# Programmable_Delay_Line.net
KiCad netlist of a schematic drawn in Altium Designer
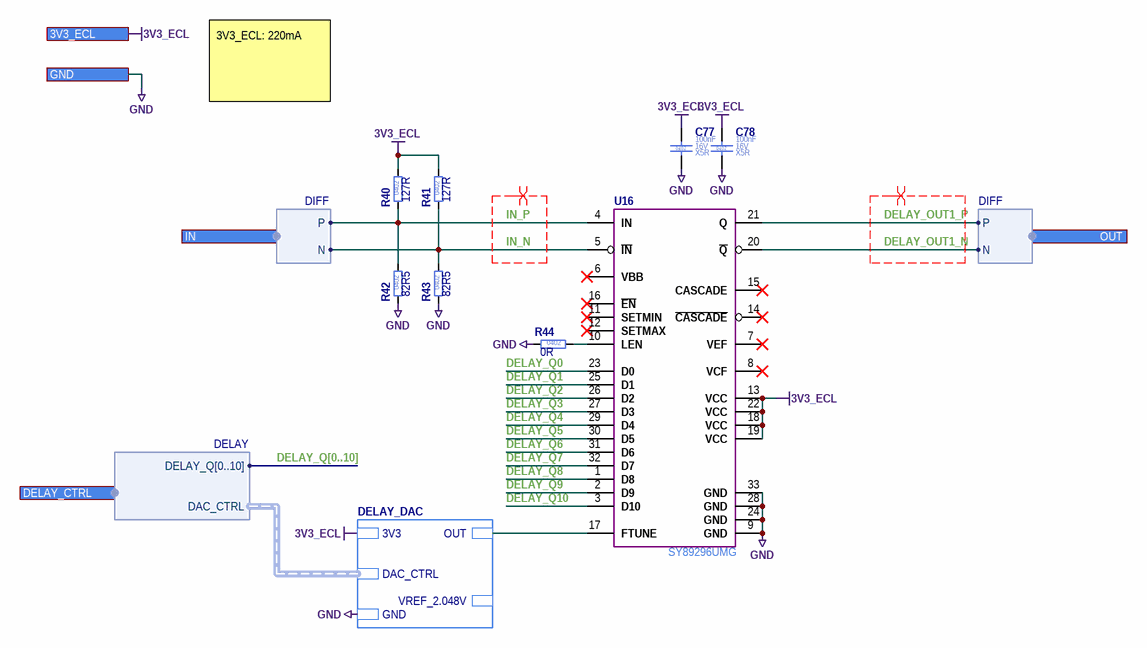
[diagram p0: Programmable_Delay_Line.SchDoc]

(export (version "E")
  (design (tool "Eeschema 10.0.6"))
  (components
    (comp (ref "C77")
      (value "C_100NF_16V_X5R_0402_10")
      (footprint "C_0402_1005")
      (description "Ceramic Capacitor")
      (fields
        (field (name "CASE/PACKAGE") "0402")
        (field (name "VOLTAGE RATING (DC)") "16V")
        (field (name "DIELECTRIC") "X5R")
        (field (name "CAPACITANCE") "100nF")
        (field (name "TOLERANCE") "10%")
        (field (name "MANUFACTURER PART NUMBER") "EMK105BJ104KV-F")
      )
      (libsource (lib "7Sigma") (part "C"))
    )
    (comp (ref "C78")
      (value "C_100NF_16V_X5R_0402_10")
      (footprint "C_0402_1005")
      (description "Ceramic Capacitor")
      (fields
        (field (name "CASE/PACKAGE") "0402")
        (field (name "VOLTAGE RATING (DC)") "16V")
        (field (name "DIELECTRIC") "X5R")
        (field (name "CAPACITANCE") "100nF")
        (field (name "TOLERANCE") "10%")
        (field (name "MANUFACTURER PART NUMBER") "EMK105BJ104KV-F")
      )
      (libsource (lib "7Sigma") (part "C"))
    )
    (comp (ref "R40")
      (value "R_127R_0402_1")
      (footprint "R_0402_1005")
      (description "Thick Film Resistor")
      (fields
        (field (name "RESISTANCE") "127R")
        (field (name "CASE/PACKAGE") "0402")
        (field (name "TOLERANCE") "1%")
        (field (name "MANUFACTURER") "Yageo")
      )
      (libsource (lib "7Sigma") (part "R"))
    )
    (comp (ref "R41")
      (value "R_127R_0402_1")
      (footprint "R_0402_1005")
      (description "Thick Film Resistor")
      (fields
        (field (name "RESISTANCE") "127R")
        (field (name "CASE/PACKAGE") "0402")
        (field (name "TOLERANCE") "1%")
        (field (name "MANUFACTURER") "Yageo")
      )
      (libsource (lib "7Sigma") (part "R"))
    )
    (comp (ref "R42")
      (value "R_82R5_0402_1")
      (footprint "R_0402_1005")
      (description "Thick Film Resistor")
      (fields
        (field (name "RESISTANCE") "82R5")
        (field (name "CASE/PACKAGE") "0402")
        (field (name "TOLERANCE") "1%")
        (field (name "MANUFACTURER") "Yageo")
      )
      (libsource (lib "7Sigma") (part "R"))
    )
    (comp (ref "R43")
      (value "R_82R5_0402_1")
      (footprint "R_0402_1005")
      (description "Thick Film Resistor")
      (fields
        (field (name "RESISTANCE") "82R5")
        (field (name "CASE/PACKAGE") "0402")
        (field (name "TOLERANCE") "1%")
        (field (name "MANUFACTURER") "Yageo")
      )
      (libsource (lib "7Sigma") (part "R"))
    )
    (comp (ref "R44")
      (value "R_0R_0402_1")
      (footprint "R_0402_1005")
      (description "Thick Film Resistor")
      (fields
        (field (name "RESISTANCE") "0R")
        (field (name "CASE/PACKAGE") "0402")
        (field (name "TOLERANCE") "1%")
        (field (name "MANUFACTURER") "Yageo")
      )
      (libsource (lib "7Sigma") (part "R"))
    )
    (comp (ref "U16")
      (value "SY89296UMG")
      (footprint "QFN50P500X500X100_HS-33N")
      (description "Delay Lines/Timing Elements 2.5V/3.3V PECL Delay Line")
      (fields
        (field (name "MANUFACTURER") "Microchip")
        (field (name "MANUFACTURER PART NUMBER") "SY89296UMG")
      )
      (libsource (lib "7Sigma") (part "SY89296U"))
    )
  )
  (nets
    (net (code "5") (name "/DELAY_OUT1_N") (class "Default")
      (node (ref "U16") (pin "20") (pinfunction "Q_20") (pintype "passive"))
    )
    (net (code "6") (name "/DELAY_OUT1_P") (class "Default")
      (node (ref "U16") (pin "21") (pinfunction "Q_21") (pintype "passive"))
    )
    (net (code "7") (name "/DELAY_Q0") (class "Default")
      (node (ref "U16") (pin "23") (pinfunction "D0_23") (pintype "passive"))
    )
    (net (code "8") (name "/DELAY_Q1") (class "Default")
      (node (ref "U16") (pin "25") (pinfunction "D1_25") (pintype "passive"))
    )
    (net (code "9") (name "/DELAY_Q2") (class "Default")
      (node (ref "U16") (pin "26") (pinfunction "D2_26") (pintype "passive"))
    )
    (net (code "10") (name "/DELAY_Q3") (class "Default")
      (node (ref "U16") (pin "27") (pinfunction "D3_27") (pintype "passive"))
    )
    (net (code "11") (name "/DELAY_Q4") (class "Default")
      (node (ref "U16") (pin "29") (pinfunction "D4_29") (pintype "passive"))
    )
    (net (code "12") (name "/DELAY_Q5") (class "Default")
      (node (ref "U16") (pin "30") (pinfunction "D5_30") (pintype "passive"))
    )
    (net (code "13") (name "/DELAY_Q6") (class "Default")
      (node (ref "U16") (pin "31") (pinfunction "D6_31") (pintype "passive"))
    )
    (net (code "14") (name "/DELAY_Q7") (class "Default")
      (node (ref "U16") (pin "32") (pinfunction "D7_32") (pintype "passive"))
    )
    (net (code "15") (name "/DELAY_Q8") (class "Default")
      (node (ref "U16") (pin "1") (pinfunction "D8_1") (pintype "passive"))
    )
    (net (code "16") (name "/DELAY_Q9") (class "Default")
      (node (ref "U16") (pin "2") (pinfunction "D9_2") (pintype "passive"))
    )
    (net (code "17") (name "/DELAY_Q10") (class "Default")
      (node (ref "U16") (pin "3") (pinfunction "D10_3") (pintype "passive"))
    )
    (net (code "19") (name "/IN_N") (class "Default")
      (node (ref "R41") (pin "1") (pinfunction "1_1") (pintype "passive"))
      (node (ref "R43") (pin "2") (pinfunction "2_2") (pintype "passive"))
      (node (ref "U16") (pin "5") (pinfunction "IN_5") (pintype "passive"))
    )
    (net (code "20") (name "/IN_P") (class "Default")
      (node (ref "R40") (pin "1") (pinfunction "1_1") (pintype "passive"))
      (node (ref "R42") (pin "2") (pinfunction "2_2") (pintype "passive"))
      (node (ref "U16") (pin "4") (pinfunction "IN_4") (pintype "passive"))
    )
    (net (code "21") (name "/OUT") (class "Default")
      (node (ref "U16") (pin "17") (pinfunction "FTUNE_17") (pintype "passive"))
    )
    (net (code "25") (name "3V3_ECL") (class "Default")
      (node (ref "C77") (pin "1") (pinfunction "1_1") (pintype "passive"))
      (node (ref "C78") (pin "1") (pinfunction "1_1") (pintype "passive"))
      (node (ref "R40") (pin "2") (pinfunction "2_2") (pintype "passive"))
      (node (ref "R41") (pin "2") (pinfunction "2_2") (pintype "passive"))
      (node (ref "U16") (pin "13") (pinfunction "VCC_13") (pintype "passive"))
      (node (ref "U16") (pin "18") (pinfunction "VCC_18") (pintype "passive"))
      (node (ref "U16") (pin "19") (pinfunction "VCC_19") (pintype "passive"))
      (node (ref "U16") (pin "22") (pinfunction "VCC_22") (pintype "passive"))
    )
    (net (code "26") (name "GND") (class "Default")
      (node (ref "C77") (pin "2") (pinfunction "2_2") (pintype "passive"))
      (node (ref "C78") (pin "2") (pinfunction "2_2") (pintype "passive"))
      (node (ref "R42") (pin "1") (pinfunction "1_1") (pintype "passive"))
      (node (ref "R43") (pin "1") (pinfunction "1_1") (pintype "passive"))
      (node (ref "R44") (pin "1") (pinfunction "1_1") (pintype "passive"))
      (node (ref "U16") (pin "24") (pinfunction "GND_24") (pintype "passive"))
      (node (ref "U16") (pin "28") (pinfunction "GND_28") (pintype "passive"))
      (node (ref "U16") (pin "33") (pinfunction "GND_33") (pintype "passive"))
      (node (ref "U16") (pin "9") (pinfunction "GND_9") (pintype "passive"))
    )
    (net (code "27") (name "Net-(U16-LEN)") (class "Default")
      (node (ref "R44") (pin "2") (pinfunction "2_2") (pintype "passive"))
      (node (ref "U16") (pin "10") (pinfunction "LEN_10") (pintype "passive"))
    )
    (net (code "28") (name "unconnected-(U16-CASCADE-Pad14)") (class "Default")
      (node (ref "U16") (pin "14") (pinfunction "CASCADE_14") (pintype "passive+no_connect"))
    )
    (net (code "29") (name "unconnected-(U16-CASCADE-Pad15)") (class "Default")
      (node (ref "U16") (pin "15") (pinfunction "CASCADE_15") (pintype "passive+no_connect"))
    )
    (net (code "30") (name "unconnected-(U16-EN-Pad16)") (class "Default")
      (node (ref "U16") (pin "16") (pinfunction "EN_16") (pintype "passive+no_connect"))
    )
    (net (code "31") (name "unconnected-(U16-SETMAX-Pad12)") (class "Default")
      (node (ref "U16") (pin "12") (pinfunction "SETMAX_12") (pintype "passive+no_connect"))
    )
    (net (code "32") (name "unconnected-(U16-SETMIN-Pad11)") (class "Default")
      (node (ref "U16") (pin "11") (pinfunction "SETMIN_11") (pintype "passive+no_connect"))
    )
    (net (code "33") (name "unconnected-(U16-VBB-Pad6)") (class "Default")
      (node (ref "U16") (pin "6") (pinfunction "VBB_6") (pintype "passive+no_connect"))
    )
    (net (code "34") (name "unconnected-(U16-VCF-Pad8)") (class "Default")
      (node (ref "U16") (pin "8") (pinfunction "VCF_8") (pintype "passive+no_connect"))
    )
    (net (code "35") (name "unconnected-(U16-VEF-Pad7)") (class "Default")
      (node (ref "U16") (pin "7") (pinfunction "VEF_7") (pintype "passive+no_connect"))
    )
  )
)
